# Sheet1.net
KiCad netlist of a schematic drawn in Altium Designer
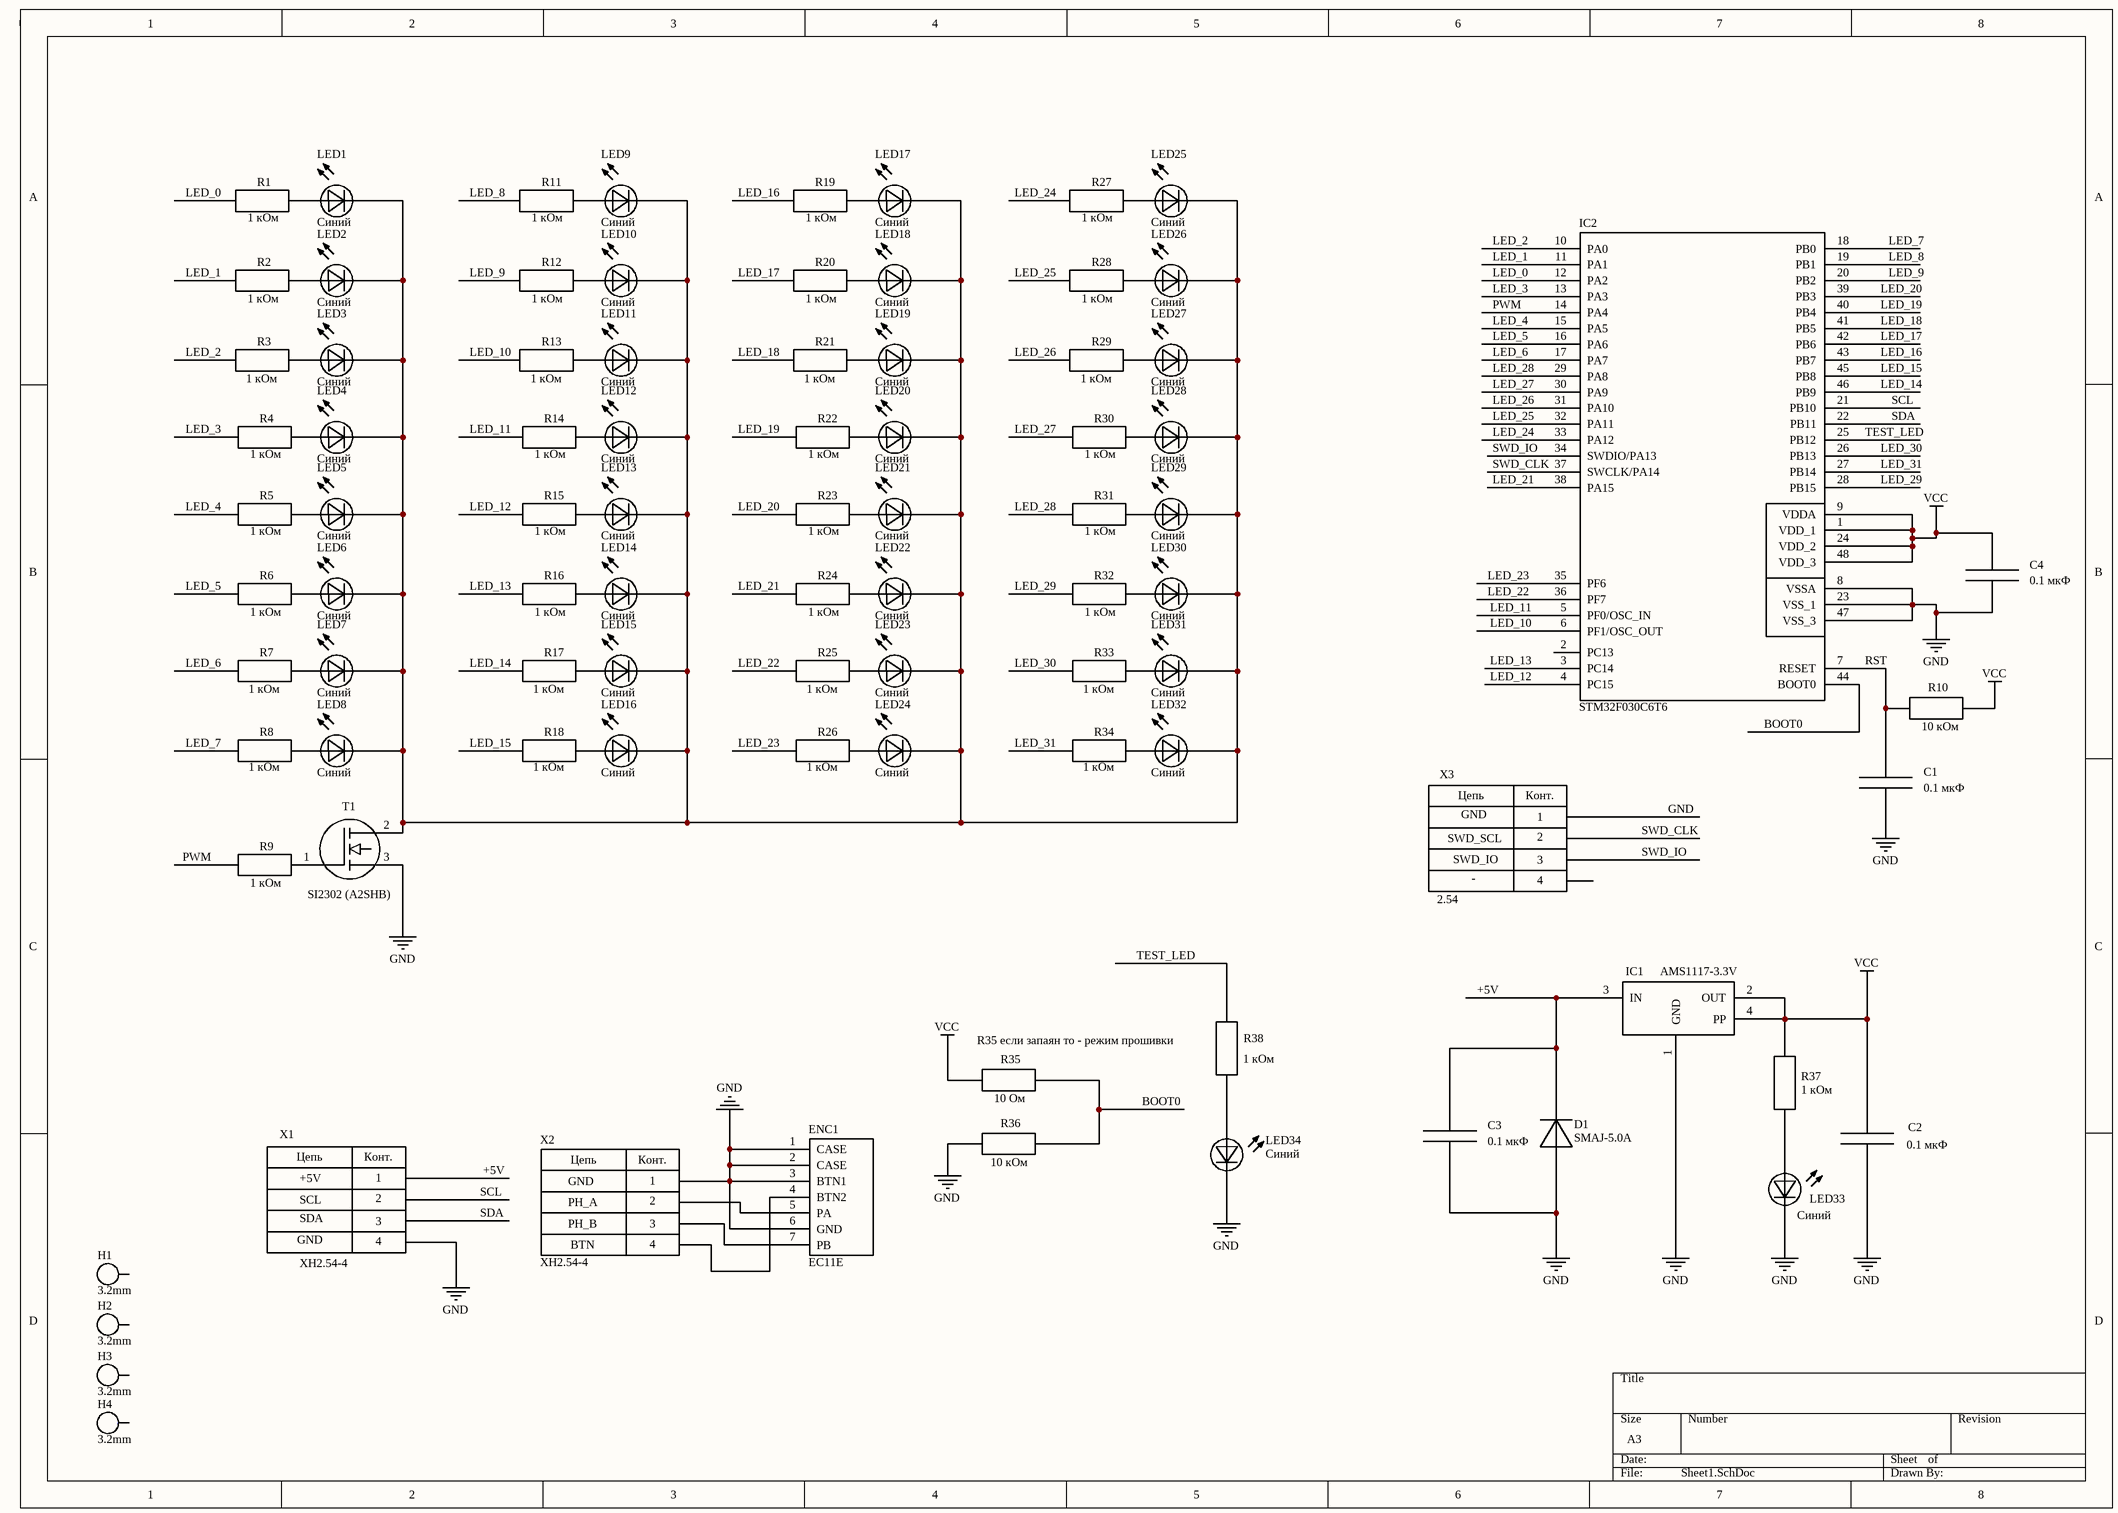
[diagram p0: Sheet1.SchDoc]

(export (version "E")
  (design (tool "Eeschema 10.0.6"))
  (components
    (comp (ref "C1")
      (value "0.1 мкФ")
      (footprint "Конденсатор SMD Case 0805")
      (libsource (lib "S83") (part "Конденсатор"))
    )
    (comp (ref "C2")
      (value "0.1 мкФ")
      (footprint "Конденсатор SMD Case 1206")
      (libsource (lib "S83") (part "Конденсатор"))
    )
    (comp (ref "C3")
      (value "0.1 мкФ")
      (footprint "Конденсатор SMD Case 0805")
      (libsource (lib "S83") (part "Конденсатор"))
    )
    (comp (ref "C4")
      (value "0.1 мкФ")
      (footprint "Конденсатор SMD Case 0805")
      (libsource (lib "S83") (part "Конденсатор"))
    )
    (comp (ref "D1") (value "SMAJ-5.0A") (footprint "Диод SS14") (libsource (lib "S83") (part "Диод")))
    (comp (ref "ENC1") (value "EC11E") (footprint "Encoder") (libsource (lib "S83") (part "Encoder_01")))
    (comp (ref "H1")
      (value "3.2mm")
      (footprint "Отверстие 3,2")
      (libsource (lib "S83") (part "Отверстие монтажное"))
    )
    (comp (ref "H2")
      (value "3.2mm")
      (footprint "Отверстие 3,2")
      (libsource (lib "S83") (part "Отверстие монтажное"))
    )
    (comp (ref "H3")
      (value "3.2mm")
      (footprint "Отверстие 3,2")
      (libsource (lib "S83") (part "Отверстие монтажное"))
    )
    (comp (ref "H4")
      (value "3.2mm")
      (footprint "Отверстие 3,2")
      (libsource (lib "S83") (part "Отверстие монтажное"))
    )
    (comp (ref "IC1")
      (value "AMS1117-3.3V")
      (footprint "SOT-223")
      (libsource (lib "S83_IC") (part "AMS1117"))
    )
    (comp (ref "IC2")
      (value "STM32F030С6T6")
      (footprint "TQFP-48")
      (libsource (lib "S83_IC") (part "STM32F030"))
    )
    (comp (ref "LED1")
      (value "Синий")
      (footprint "Светодиод  3x2 mm")
      (libsource (lib "S83") (part "Светодиод"))
    )
    (comp (ref "LED2")
      (value "Синий")
      (footprint "Светодиод  3x2 mm")
      (libsource (lib "S83") (part "Светодиод"))
    )
    (comp (ref "LED3")
      (value "Синий")
      (footprint "Светодиод  3x2 mm")
      (libsource (lib "S83") (part "Светодиод"))
    )
    (comp (ref "LED4")
      (value "Синий")
      (footprint "Светодиод  3x2 mm")
      (libsource (lib "S83") (part "Светодиод"))
    )
    (comp (ref "LED5")
      (value "Синий")
      (footprint "Светодиод  3x2 mm")
      (libsource (lib "S83") (part "Светодиод"))
    )
    (comp (ref "LED6")
      (value "Синий")
      (footprint "Светодиод  3x2 mm")
      (libsource (lib "S83") (part "Светодиод"))
    )
    (comp (ref "LED7")
      (value "Синий")
      (footprint "Светодиод  3x2 mm")
      (libsource (lib "S83") (part "Светодиод"))
    )
    (comp (ref "LED8")
      (value "Синий")
      (footprint "Светодиод  3x2 mm")
      (libsource (lib "S83") (part "Светодиод"))
    )
    (comp (ref "LED9")
      (value "Синий")
      (footprint "Светодиод  3x2 mm")
      (libsource (lib "S83") (part "Светодиод"))
    )
    (comp (ref "LED10")
      (value "Синий")
      (footprint "Светодиод  3x2 mm")
      (libsource (lib "S83") (part "Светодиод"))
    )
    (comp (ref "LED11")
      (value "Синий")
      (footprint "Светодиод  3x2 mm")
      (libsource (lib "S83") (part "Светодиод"))
    )
    (comp (ref "LED12")
      (value "Синий")
      (footprint "Светодиод  3x2 mm")
      (libsource (lib "S83") (part "Светодиод"))
    )
    (comp (ref "LED13")
      (value "Синий")
      (footprint "Светодиод  3x2 mm")
      (libsource (lib "S83") (part "Светодиод"))
    )
    (comp (ref "LED14")
      (value "Синий")
      (footprint "Светодиод  3x2 mm")
      (libsource (lib "S83") (part "Светодиод"))
    )
    (comp (ref "LED15")
      (value "Синий")
      (footprint "Светодиод  3x2 mm")
      (libsource (lib "S83") (part "Светодиод"))
    )
    (comp (ref "LED16")
      (value "Синий")
      (footprint "Светодиод  3x2 mm")
      (libsource (lib "S83") (part "Светодиод"))
    )
    (comp (ref "LED17")
      (value "Синий")
      (footprint "Светодиод  3x2 mm")
      (libsource (lib "S83") (part "Светодиод"))
    )
    (comp (ref "LED18")
      (value "Синий")
      (footprint "Светодиод  3x2 mm")
      (libsource (lib "S83") (part "Светодиод"))
    )
    (comp (ref "LED19")
      (value "Синий")
      (footprint "Светодиод  3x2 mm")
      (libsource (lib "S83") (part "Светодиод"))
    )
    (comp (ref "LED20")
      (value "Синий")
      (footprint "Светодиод  3x2 mm")
      (libsource (lib "S83") (part "Светодиод"))
    )
    (comp (ref "LED21")
      (value "Синий")
      (footprint "Светодиод  3x2 mm")
      (libsource (lib "S83") (part "Светодиод"))
    )
    (comp (ref "LED22")
      (value "Синий")
      (footprint "Светодиод  3x2 mm")
      (libsource (lib "S83") (part "Светодиод"))
    )
    (comp (ref "LED23")
      (value "Синий")
      (footprint "Светодиод  3x2 mm")
      (libsource (lib "S83") (part "Светодиод"))
    )
    (comp (ref "LED24")
      (value "Синий")
      (footprint "Светодиод  3x2 mm")
      (libsource (lib "S83") (part "Светодиод"))
    )
    (comp (ref "LED25")
      (value "Синий")
      (footprint "Светодиод  3x2 mm")
      (libsource (lib "S83") (part "Светодиод"))
    )
    (comp (ref "LED26")
      (value "Синий")
      (footprint "Светодиод  3x2 mm")
      (libsource (lib "S83") (part "Светодиод"))
    )
    (comp (ref "LED27")
      (value "Синий")
      (footprint "Светодиод  3x2 mm")
      (libsource (lib "S83") (part "Светодиод"))
    )
    (comp (ref "LED28")
      (value "Синий")
      (footprint "Светодиод  3x2 mm")
      (libsource (lib "S83") (part "Светодиод"))
    )
    (comp (ref "LED29")
      (value "Синий")
      (footprint "Светодиод  3x2 mm")
      (libsource (lib "S83") (part "Светодиод"))
    )
    (comp (ref "LED30")
      (value "Синий")
      (footprint "Светодиод  3x2 mm")
      (libsource (lib "S83") (part "Светодиод"))
    )
    (comp (ref "LED31")
      (value "Синий")
      (footprint "Светодиод  3x2 mm")
      (libsource (lib "S83") (part "Светодиод"))
    )
    (comp (ref "LED32")
      (value "Синий")
      (footprint "Светодиод  3x2 mm")
      (libsource (lib "S83") (part "Светодиод"))
    )
    (comp (ref "LED33")
      (value "Синий")
      (footprint "SMD 1206 Светодиод ВАЙТ")
      (libsource (lib "S83") (part "Светодиод"))
    )
    (comp (ref "LED34")
      (value "Синий")
      (footprint "SMD 1206 Светодиод ВАЙТ")
      (libsource (lib "S83") (part "Светодиод"))
    )
    (comp (ref "R1")
      (value "1 кОм")
      (footprint "SMD 0805 Резистор")
      (libsource (lib "S83") (part "Резистор"))
    )
    (comp (ref "R2")
      (value "1 кОм")
      (footprint "SMD 0805 Резистор")
      (libsource (lib "S83") (part "Резистор"))
    )
    (comp (ref "R3")
      (value "1 кОм")
      (footprint "SMD 0805 Резистор")
      (libsource (lib "S83") (part "Резистор"))
    )
    (comp (ref "R4")
      (value "1 кОм")
      (footprint "SMD 0805 Резистор")
      (libsource (lib "S83") (part "Резистор"))
    )
    (comp (ref "R5")
      (value "1 кОм")
      (footprint "SMD 0805 Резистор")
      (libsource (lib "S83") (part "Резистор"))
    )
    (comp (ref "R6")
      (value "1 кОм")
      (footprint "SMD 0805 Резистор")
      (libsource (lib "S83") (part "Резистор"))
    )
    (comp (ref "R7")
      (value "1 кОм")
      (footprint "SMD 0805 Резистор")
      (libsource (lib "S83") (part "Резистор"))
    )
    (comp (ref "R8")
      (value "1 кОм")
      (footprint "SMD 0805 Резистор")
      (libsource (lib "S83") (part "Резистор"))
    )
    (comp (ref "R9")
      (value "1 кОм")
      (footprint "SMD 0805 Резистор")
      (libsource (lib "S83") (part "Резистор"))
    )
    (comp (ref "R10")
      (value "10 кОм")
      (footprint "SMD 0805 Резистор")
      (libsource (lib "S83") (part "Резистор"))
    )
    (comp (ref "R11")
      (value "1 кОм")
      (footprint "SMD 0805 Резистор")
      (libsource (lib "S83") (part "Резистор"))
    )
    (comp (ref "R12")
      (value "1 кОм")
      (footprint "SMD 0805 Резистор")
      (libsource (lib "S83") (part "Резистор"))
    )
    (comp (ref "R13")
      (value "1 кОм")
      (footprint "SMD 0805 Резистор")
      (libsource (lib "S83") (part "Резистор"))
    )
    (comp (ref "R14")
      (value "1 кОм")
      (footprint "SMD 0805 Резистор")
      (libsource (lib "S83") (part "Резистор"))
    )
    (comp (ref "R15")
      (value "1 кОм")
      (footprint "SMD 0805 Резистор")
      (libsource (lib "S83") (part "Резистор"))
    )
    (comp (ref "R16")
      (value "1 кОм")
      (footprint "SMD 0805 Резистор")
      (libsource (lib "S83") (part "Резистор"))
    )
    (comp (ref "R17")
      (value "1 кОм")
      (footprint "SMD 0805 Резистор")
      (libsource (lib "S83") (part "Резистор"))
    )
    (comp (ref "R18")
      (value "1 кОм")
      (footprint "SMD 0805 Резистор")
      (libsource (lib "S83") (part "Резистор"))
    )
    (comp (ref "R19")
      (value "1 кОм")
      (footprint "SMD 0805 Резистор")
      (libsource (lib "S83") (part "Резистор"))
    )
    (comp (ref "R20")
      (value "1 кОм")
      (footprint "SMD 0805 Резистор")
      (libsource (lib "S83") (part "Резистор"))
    )
    (comp (ref "R21")
      (value "1 кОм")
      (footprint "SMD 0805 Резистор")
      (libsource (lib "S83") (part "Резистор"))
    )
    (comp (ref "R22")
      (value "1 кОм")
      (footprint "SMD 0805 Резистор")
      (libsource (lib "S83") (part "Резистор"))
    )
    (comp (ref "R23")
      (value "1 кОм")
      (footprint "SMD 0805 Резистор")
      (libsource (lib "S83") (part "Резистор"))
    )
    (comp (ref "R24")
      (value "1 кОм")
      (footprint "SMD 0805 Резистор")
      (libsource (lib "S83") (part "Резистор"))
    )
    (comp (ref "R25")
      (value "1 кОм")
      (footprint "SMD 0805 Резистор")
      (libsource (lib "S83") (part "Резистор"))
    )
    (comp (ref "R26")
      (value "1 кОм")
      (footprint "SMD 0805 Резистор")
      (libsource (lib "S83") (part "Резистор"))
    )
    (comp (ref "R27")
      (value "1 кОм")
      (footprint "SMD 0805 Резистор")
      (libsource (lib "S83") (part "Резистор"))
    )
    (comp (ref "R28")
      (value "1 кОм")
      (footprint "SMD 0805 Резистор")
      (libsource (lib "S83") (part "Резистор"))
    )
    (comp (ref "R29")
      (value "1 кОм")
      (footprint "SMD 0805 Резистор")
      (libsource (lib "S83") (part "Резистор"))
    )
    (comp (ref "R30")
      (value "1 кОм")
      (footprint "SMD 0805 Резистор")
      (libsource (lib "S83") (part "Резистор"))
    )
    (comp (ref "R31")
      (value "1 кОм")
      (footprint "SMD 0805 Резистор")
      (libsource (lib "S83") (part "Резистор"))
    )
    (comp (ref "R32")
      (value "1 кОм")
      (footprint "SMD 0805 Резистор")
      (libsource (lib "S83") (part "Резистор"))
    )
    (comp (ref "R33")
      (value "1 кОм")
      (footprint "SMD 0805 Резистор")
      (libsource (lib "S83") (part "Резистор"))
    )
    (comp (ref "R34")
      (value "1 кОм")
      (footprint "SMD 0805 Резистор")
      (libsource (lib "S83") (part "Резистор"))
    )
    (comp (ref "R35")
      (value "10 Ом")
      (footprint "SMD 0805 Резистор")
      (libsource (lib "S83") (part "Резистор"))
    )
    (comp (ref "R36")
      (value "10 кОм")
      (footprint "SMD 0805 Резистор")
      (libsource (lib "S83") (part "Резистор"))
    )
    (comp (ref "R37")
      (value "1 кОм")
      (footprint "SMD 0805 Резистор")
      (libsource (lib "S83") (part "Резистор"))
    )
    (comp (ref "R38")
      (value "1 кОм")
      (footprint "SMD 0805 Резистор")
      (libsource (lib "S83") (part "Резистор"))
    )
    (comp (ref "T1")
      (value "SI2302 (A2SHB)")
      (footprint "SMD SOT-23 Транзистор 3 pin")
      (libsource (lib "S83") (part "Транзистор MOSFET N-конал (как n-p-n)"))
    )
    (comp (ref "X1")
      (value "XH2.54-4")
      (footprint "(1x4) PIN XH 2.54 HEADR")
      (libsource (lib "S83_connectors") (part "(1x4) pin XH 2.54 Header"))
    )
    (comp (ref "X2")
      (value "XH2.54-4")
      (footprint "(1x4) PIN XH 2.54 HEADR")
      (libsource (lib "S83_connectors") (part "(1x4) pin XH 2.54 Header"))
    )
    (comp (ref "X3")
      (value "2.54")
      (footprint "(1x4)PIN 2.54 HEADR")
      (libsource (lib "S83_connectors") (part "(1x4) pin XH 2.54 Header"))
    )
  )
  (nets
    (net (code "1") (name "/+5V") (class "Default")
      (node (ref "C3") (pin "1") (pinfunction "+_1") (pintype "passive"))
      (node (ref "D1") (pin "2") (pinfunction "K_2") (pintype "passive"))
      (node (ref "IC1") (pin "3") (pinfunction "IN_3") (pintype "passive"))
      (node (ref "X1") (pin "1") (pinfunction "1_1") (pintype "passive"))
    )
    (net (code "2") (name "/BOOT0") (class "Default")
      (node (ref "IC2") (pin "44") (pinfunction "BOOT0_44") (pintype "passive"))
      (node (ref "R35") (pin "2") (pinfunction "right_2") (pintype "passive"))
      (node (ref "R36") (pin "2") (pinfunction "right_2") (pintype "passive"))
    )
    (net (code "3") (name "/LED_0") (class "Default")
      (node (ref "IC2") (pin "12") (pinfunction "PA2_12") (pintype "passive"))
      (node (ref "R1") (pin "1") (pinfunction "left_1") (pintype "passive"))
    )
    (net (code "4") (name "/LED_1") (class "Default")
      (node (ref "IC2") (pin "11") (pinfunction "PA1_11") (pintype "passive"))
      (node (ref "R2") (pin "1") (pinfunction "left_1") (pintype "passive"))
    )
    (net (code "5") (name "/LED_2") (class "Default")
      (node (ref "IC2") (pin "10") (pinfunction "PA0_10") (pintype "passive"))
      (node (ref "R3") (pin "1") (pinfunction "left_1") (pintype "passive"))
    )
    (net (code "6") (name "/LED_3") (class "Default")
      (node (ref "IC2") (pin "13") (pinfunction "PA3_13") (pintype "passive"))
      (node (ref "R4") (pin "1") (pinfunction "left_1") (pintype "passive"))
    )
    (net (code "7") (name "/LED_4") (class "Default")
      (node (ref "IC2") (pin "15") (pinfunction "PA5_15") (pintype "passive"))
      (node (ref "R5") (pin "1") (pinfunction "left_1") (pintype "passive"))
    )
    (net (code "8") (name "/LED_5") (class "Default")
      (node (ref "IC2") (pin "16") (pinfunction "PA6_16") (pintype "passive"))
      (node (ref "R6") (pin "1") (pinfunction "left_1") (pintype "passive"))
    )
    (net (code "9") (name "/LED_6") (class "Default")
      (node (ref "IC2") (pin "17") (pinfunction "PA7_17") (pintype "passive"))
      (node (ref "R7") (pin "1") (pinfunction "left_1") (pintype "passive"))
    )
    (net (code "10") (name "/LED_7") (class "Default")
      (node (ref "IC2") (pin "18") (pinfunction "PB0_18") (pintype "passive"))
      (node (ref "R8") (pin "1") (pinfunction "left_1") (pintype "passive"))
    )
    (net (code "11") (name "/LED_8") (class "Default")
      (node (ref "IC2") (pin "19") (pinfunction "PB1_19") (pintype "passive"))
      (node (ref "R11") (pin "1") (pinfunction "left_1") (pintype "passive"))
    )
    (net (code "12") (name "/LED_9") (class "Default")
      (node (ref "IC2") (pin "20") (pinfunction "PB2_20") (pintype "passive"))
      (node (ref "R12") (pin "1") (pinfunction "left_1") (pintype "passive"))
    )
    (net (code "13") (name "/LED_10") (class "Default")
      (node (ref "IC2") (pin "6") (pinfunction "PF1/OSC_OUT_6") (pintype "passive"))
      (node (ref "R13") (pin "1") (pinfunction "left_1") (pintype "passive"))
    )
    (net (code "14") (name "/LED_11") (class "Default")
      (node (ref "IC2") (pin "5") (pinfunction "PF0/OSC_IN_5") (pintype "passive"))
      (node (ref "R14") (pin "1") (pinfunction "left_1") (pintype "passive"))
    )
    (net (code "15") (name "/LED_12") (class "Default")
      (node (ref "IC2") (pin "4") (pinfunction "PC15_4") (pintype "passive"))
      (node (ref "R15") (pin "1") (pinfunction "left_1") (pintype "passive"))
    )
    (net (code "16") (name "/LED_13") (class "Default")
      (node (ref "IC2") (pin "3") (pinfunction "PC14_3") (pintype "passive"))
      (node (ref "R16") (pin "1") (pinfunction "left_1") (pintype "passive"))
    )
    (net (code "17") (name "/LED_14") (class "Default")
      (node (ref "IC2") (pin "46") (pinfunction "PB9_46") (pintype "passive"))
      (node (ref "R17") (pin "1") (pinfunction "left_1") (pintype "passive"))
    )
    (net (code "18") (name "/LED_15") (class "Default")
      (node (ref "IC2") (pin "45") (pinfunction "PB8_45") (pintype "passive"))
      (node (ref "R18") (pin "1") (pinfunction "left_1") (pintype "passive"))
    )
    (net (code "19") (name "/LED_16") (class "Default")
      (node (ref "IC2") (pin "43") (pinfunction "PB7_43") (pintype "passive"))
      (node (ref "R19") (pin "1") (pinfunction "left_1") (pintype "passive"))
    )
    (net (code "20") (name "/LED_17") (class "Default")
      (node (ref "IC2") (pin "42") (pinfunction "PB6_42") (pintype "passive"))
      (node (ref "R20") (pin "1") (pinfunction "left_1") (pintype "passive"))
    )
    (net (code "21") (name "/LED_18") (class "Default")
      (node (ref "IC2") (pin "41") (pinfunction "PB5_41") (pintype "passive"))
      (node (ref "R21") (pin "1") (pinfunction "left_1") (pintype "passive"))
    )
    (net (code "22") (name "/LED_19") (class "Default")
      (node (ref "IC2") (pin "40") (pinfunction "PB4_40") (pintype "passive"))
      (node (ref "R22") (pin "1") (pinfunction "left_1") (pintype "passive"))
    )
    (net (code "23") (name "/LED_20") (class "Default")
      (node (ref "IC2") (pin "39") (pinfunction "PB3_39") (pintype "passive"))
      (node (ref "R23") (pin "1") (pinfunction "left_1") (pintype "passive"))
    )
    (net (code "24") (name "/LED_21") (class "Default")
      (node (ref "IC2") (pin "38") (pinfunction "PA15_38") (pintype "passive"))
      (node (ref "R24") (pin "1") (pinfunction "left_1") (pintype "passive"))
    )
    (net (code "25") (name "/LED_22") (class "Default")
      (node (ref "IC2") (pin "36") (pinfunction "PF7_36") (pintype "passive"))
      (node (ref "R25") (pin "1") (pinfunction "left_1") (pintype "passive"))
    )
    (net (code "26") (name "/LED_23") (class "Default")
      (node (ref "IC2") (pin "35") (pinfunction "PF6_35") (pintype "passive"))
      (node (ref "R26") (pin "1") (pinfunction "left_1") (pintype "passive"))
    )
    (net (code "27") (name "/LED_24") (class "Default")
      (node (ref "IC2") (pin "33") (pinfunction "PA12_33") (pintype "passive"))
      (node (ref "R27") (pin "1") (pinfunction "left_1") (pintype "passive"))
    )
    (net (code "28") (name "/LED_25") (class "Default")
      (node (ref "IC2") (pin "32") (pinfunction "PA11_32") (pintype "passive"))
      (node (ref "R28") (pin "1") (pinfunction "left_1") (pintype "passive"))
    )
    (net (code "29") (name "/LED_26") (class "Default")
      (node (ref "IC2") (pin "31") (pinfunction "PA10_31") (pintype "passive"))
      (node (ref "R29") (pin "1") (pinfunction "left_1") (pintype "passive"))
    )
    (net (code "30") (name "/LED_27") (class "Default")
      (node (ref "IC2") (pin "30") (pinfunction "PA9_30") (pintype "passive"))
      (node (ref "R30") (pin "1") (pinfunction "left_1") (pintype "passive"))
    )
    (net (code "31") (name "/LED_28") (class "Default")
      (node (ref "IC2") (pin "29") (pinfunction "PA8_29") (pintype "passive"))
      (node (ref "R31") (pin "1") (pinfunction "left_1") (pintype "passive"))
    )
    (net (code "32") (name "/LED_29") (class "Default")
      (node (ref "IC2") (pin "28") (pinfunction "PB15_28") (pintype "passive"))
      (node (ref "R32") (pin "1") (pinfunction "left_1") (pintype "passive"))
    )
    (net (code "33") (name "/LED_30") (class "Default")
      (node (ref "IC2") (pin "26") (pinfunction "PB13_26") (pintype "passive"))
      (node (ref "R33") (pin "1") (pinfunction "left_1") (pintype "passive"))
    )
    (net (code "34") (name "/LED_31") (class "Default")
      (node (ref "IC2") (pin "27") (pinfunction "PB14_27") (pintype "passive"))
      (node (ref "R34") (pin "1") (pinfunction "left_1") (pintype "passive"))
    )
    (net (code "35") (name "/PWM") (class "Default")
      (node (ref "IC2") (pin "14") (pinfunction "PA4_14") (pintype "passive"))
      (node (ref "R9") (pin "1") (pinfunction "left_1") (pintype "passive"))
    )
    (net (code "36") (name "/RST") (class "Default")
      (node (ref "C1") (pin "1") (pinfunction "+_1") (pintype "passive"))
      (node (ref "IC2") (pin "7") (pinfunction "RESET_7") (pintype "passive"))
      (node (ref "R10") (pin "1") (pinfunction "left_1") (pintype "passive"))
    )
    (net (code "37") (name "/SCL") (class "Default")
      (node (ref "IC2") (pin "21") (pinfunction "PB10_21") (pintype "passive"))
      (node (ref "X1") (pin "2") (pinfunction "2_2") (pintype "passive"))
    )
    (net (code "38") (name "/SDA") (class "Default")
      (node (ref "IC2") (pin "22") (pinfunction "PB11_22") (pintype "passive"))
      (node (ref "X1") (pin "3") (pinfunction "3_3") (pintype "passive"))
    )
    (net (code "39") (name "/SWD_CLK") (class "Default")
      (node (ref "IC2") (pin "37") (pinfunction "SWCLK/PA14_37") (pintype "passive"))
      (node (ref "X3") (pin "2") (pinfunction "2_2") (pintype "passive"))
    )
    (net (code "40") (name "/SWD_IO") (class "Default")
      (node (ref "IC2") (pin "34") (pinfunction "SWDIO/PA13_34") (pintype "passive"))
      (node (ref "X3") (pin "3") (pinfunction "3_3") (pintype "passive"))
    )
    (net (code "41") (name "/TEST_LED") (class "Default")
      (node (ref "IC2") (pin "25") (pinfunction "PB12_25") (pintype "passive"))
      (node (ref "R38") (pin "2") (pinfunction "right_2") (pintype "passive"))
    )
    (net (code "42") (name "GND") (class "Default")
      (node (ref "C1") (pin "2") (pinfunction "-_2") (pintype "passive"))
      (node (ref "C2") (pin "2") (pinfunction "-_2") (pintype "passive"))
      (node (ref "C3") (pin "2") (pinfunction "-_2") (pintype "passive"))
      (node (ref "C4") (pin "2") (pinfunction "-_2") (pintype "passive"))
      (node (ref "D1") (pin "1") (pinfunction "А_1") (pintype "passive"))
      (node (ref "ENC1") (pin "1") (pinfunction "CASE_1") (pintype "passive"))
      (node (ref "ENC1") (pin "2") (pinfunction "CASE_2") (pintype "passive"))
      (node (ref "ENC1") (pin "3") (pinfunction "BTN1_3") (pintype "passive"))
      (node (ref "ENC1") (pin "6") (pinfunction "GND_6") (pintype "passive"))
      (node (ref "IC1") (pin "1") (pinfunction "GND_1") (pintype "passive"))
      (node (ref "IC2") (pin "23") (pinfunction "VSS_1_23") (pintype "passive"))
      (node (ref "IC2") (pin "47") (pinfunction "VSS_3_47") (pintype "passive"))
      (node (ref "IC2") (pin "8") (pinfunction "VSSA_8") (pintype "passive"))
      (node (ref "LED33") (pin "2") (pinfunction "K_2") (pintype "passive"))
      (node (ref "LED34") (pin "2") (pinfunction "K_2") (pintype "passive"))
      (node (ref "R36") (pin "1") (pinfunction "left_1") (pintype "passive"))
      (node (ref "T1") (pin "3") (pinfunction "3_3") (pintype "passive"))
      (node (ref "X1") (pin "4") (pinfunction "4_4") (pintype "passive"))
      (node (ref "X2") (pin "1") (pinfunction "1_1") (pintype "passive"))
      (node (ref "X3") (pin "1") (pinfunction "1_1") (pintype "passive"))
    )
    (net (code "43") (name "Net-(ENC1-BTN2)") (class "Default")
      (node (ref "ENC1") (pin "4") (pinfunction "BTN2_4") (pintype "passive"))
      (node (ref "X2") (pin "4") (pinfunction "4_4") (pintype "passive"))
    )
    (net (code "44") (name "Net-(ENC1-PA)") (class "Default")
      (node (ref "ENC1") (pin "5") (pinfunction "PA_5") (pintype "passive"))
      (node (ref "X2") (pin "2") (pinfunction "2_2") (pintype "passive"))
    )
    (net (code "45") (name "Net-(ENC1-PB)") (class "Default")
      (node (ref "ENC1") (pin "7") (pinfunction "PB_7") (pintype "passive"))
      (node (ref "X2") (pin "3") (pinfunction "3_3") (pintype "passive"))
    )
    (net (code "46") (name "Net-(LED1-K)") (class "Default")
      (node (ref "LED1") (pin "2") (pinfunction "K_2") (pintype "passive"))
      (node (ref "LED10") (pin "2") (pinfunction "K_2") (pintype "passive"))
      (node (ref "LED11") (pin "2") (pinfunction "K_2") (pintype "passive"))
      (node (ref "LED12") (pin "2") (pinfunction "K_2") (pintype "passive"))
      (node (ref "LED13") (pin "2") (pinfunction "K_2") (pintype "passive"))
      (node (ref "LED14") (pin "2") (pinfunction "K_2") (pintype "passive"))
      (node (ref "LED15") (pin "2") (pinfunction "K_2") (pintype "passive"))
      (node (ref "LED16") (pin "2") (pinfunction "K_2") (pintype "passive"))
      (node (ref "LED17") (pin "2") (pinfunction "K_2") (pintype "passive"))
      (node (ref "LED18") (pin "2") (pinfunction "K_2") (pintype "passive"))
      (node (ref "LED19") (pin "2") (pinfunction "K_2") (pintype "passive"))
      (node (ref "LED2") (pin "2") (pinfunction "K_2") (pintype "passive"))
      (node (ref "LED20") (pin "2") (pinfunction "K_2") (pintype "passive"))
      (node (ref "LED21") (pin "2") (pinfunction "K_2") (pintype "passive"))
      (node (ref "LED22") (pin "2") (pinfunction "K_2") (pintype "passive"))
      (node (ref "LED23") (pin "2") (pinfunction "K_2") (pintype "passive"))
      (node (ref "LED24") (pin "2") (pinfunction "K_2") (pintype "passive"))
      (node (ref "LED25") (pin "2") (pinfunction "K_2") (pintype "passive"))
      (node (ref "LED26") (pin "2") (pinfunction "K_2") (pintype "passive"))
      (node (ref "LED27") (pin "2") (pinfunction "K_2") (pintype "passive"))
      (node (ref "LED28") (pin "2") (pinfunction "K_2") (pintype "passive"))
      (node (ref "LED29") (pin "2") (pinfunction "K_2") (pintype "passive"))
      (node (ref "LED3") (pin "2") (pinfunction "K_2") (pintype "passive"))
      (node (ref "LED30") (pin "2") (pinfunction "K_2") (pintype "passive"))
      (node (ref "LED31") (pin "2") (pinfunction "K_2") (pintype "passive"))
      (node (ref "LED32") (pin "2") (pinfunction "K_2") (pintype "passive"))
      (node (ref "LED4") (pin "2") (pinfunction "K_2") (pintype "passive"))
      (node (ref "LED5") (pin "2") (pinfunction "K_2") (pintype "passive"))
      (node (ref "LED6") (pin "2") (pinfunction "K_2") (pintype "passive"))
      (node (ref "LED7") (pin "2") (pinfunction "K_2") (pintype "passive"))
      (node (ref "LED8") (pin "2") (pinfunction "K_2") (pintype "passive"))
      (node (ref "LED9") (pin "2") (pinfunction "K_2") (pintype "passive"))
      (node (ref "T1") (pin "2") (pinfunction "2_2") (pintype "passive"))
    )
    (net (code "47") (name "Net-(LED1-А)") (class "Default")
      (node (ref "LED1") (pin "1") (pinfunction "А_1") (pintype "passive"))
      (node (ref "R1") (pin "2") (pinfunction "right_2") (pintype "passive"))
    )
    (net (code "48") (name "Net-(LED2-А)") (class "Default")
      (node (ref "LED2") (pin "1") (pinfunction "А_1") (pintype "passive"))
      (node (ref "R2") (pin "2") (pinfunction "right_2") (pintype "passive"))
    )
    (net (code "49") (name "Net-(LED3-А)") (class "Default")
      (node (ref "LED3") (pin "1") (pinfunction "А_1") (pintype "passive"))
      (node (ref "R3") (pin "2") (pinfunction "right_2") (pintype "passive"))
    )
    (net (code "50") (name "Net-(LED4-А)") (class "Default")
      (node (ref "LED4") (pin "1") (pinfunction "А_1") (pintype "passive"))
      (node (ref "R4") (pin "2") (pinfunction "right_2") (pintype "passive"))
    )
    (net (code "51") (name "Net-(LED5-А)") (class "Default")
      (node (ref "LED5") (pin "1") (pinfunction "А_1") (pintype "passive"))
      (node (ref "R5") (pin "2") (pinfunction "right_2") (pintype "passive"))
    )
    (net (code "52") (name "Net-(LED6-А)") (class "Default")
      (node (ref "LED6") (pin "1") (pinfunction "А_1") (pintype "passive"))
      (node (ref "R6") (pin "2") (pinfunction "right_2") (pintype "passive"))
    )
    (net (code "53") (name "Net-(LED7-А)") (class "Default")
      (node (ref "LED7") (pin "1") (pinfunction "А_1") (pintype "passive"))
      (node (ref "R7") (pin "2") (pinfunction "right_2") (pintype "passive"))
    )
    (net (code "54") (name "Net-(LED8-А)") (class "Default")
      (node (ref "LED8") (pin "1") (pinfunction "А_1") (pintype "passive"))
      (node (ref "R8") (pin "2") (pinfunction "right_2") (pintype "passive"))
    )
    (net (code "55") (name "Net-(LED9-А)") (class "Default")
      (node (ref "LED9") (pin "1") (pinfunction "А_1") (pintype "passive"))
      (node (ref "R11") (pin "2") (pinfunction "right_2") (pintype "passive"))
    )
    (net (code "56") (name "Net-(LED10-А)") (class "Default")
      (node (ref "LED10") (pin "1") (pinfunction "А_1") (pintype "passive"))
      (node (ref "R12") (pin "2") (pinfunction "right_2") (pintype "passive"))
    )
    (net (code "57") (name "Net-(LED11-А)") (class "Default")
      (node (ref "LED11") (pin "1") (pinfunction "А_1") (pintype "passive"))
      (node (ref "R13") (pin "2") (pinfunction "right_2") (pintype "passive"))
    )
    (net (code "58") (name "Net-(LED12-А)") (class "Default")
      (node (ref "LED12") (pin "1") (pinfunction "А_1") (pintype "passive"))
      (node (ref "R14") (pin "2") (pinfunction "right_2") (pintype "passive"))
    )
    (net (code "59") (name "Net-(LED13-А)") (class "Default")
      (node (ref "LED13") (pin "1") (pinfunction "А_1") (pintype "passive"))
      (node (ref "R15") (pin "2") (pinfunction "right_2") (pintype "passive"))
    )
    (net (code "60") (name "Net-(LED14-А)") (class "Default")
      (node (ref "LED14") (pin "1") (pinfunction "А_1") (pintype "passive"))
      (node (ref "R16") (pin "2") (pinfunction "right_2") (pintype "passive"))
    )
    (net (code "61") (name "Net-(LED15-А)") (class "Default")
      (node (ref "LED15") (pin "1") (pinfunction "А_1") (pintype "passive"))
      (node (ref "R17") (pin "2") (pinfunction "right_2") (pintype "passive"))
    )
    (net (code "62") (name "Net-(LED16-А)") (class "Default")
      (node (ref "LED16") (pin "1") (pinfunction "А_1") (pintype "passive"))
      (node (ref "R18") (pin "2") (pinfunction "right_2") (pintype "passive"))
    )
    (net (code "63") (name "Net-(LED17-А)") (class "Default")
      (node (ref "LED17") (pin "1") (pinfunction "А_1") (pintype "passive"))
      (node (ref "R19") (pin "2") (pinfunction "right_2") (pintype "passive"))
    )
    (net (code "64") (name "Net-(LED18-А)") (class "Default")
      (node (ref "LED18") (pin "1") (pinfunction "А_1") (pintype "passive"))
      (node (ref "R20") (pin "2") (pinfunction "right_2") (pintype "passive"))
    )
    (net (code "65") (name "Net-(LED19-А)") (class "Default")
      (node (ref "LED19") (pin "1") (pinfunction "А_1") (pintype "passive"))
      (node (ref "R21") (pin "2") (pinfunction "right_2") (pintype "passive"))
    )
    (net (code "66") (name "Net-(LED20-А)") (class "Default")
      (node (ref "LED20") (pin "1") (pinfunction "А_1") (pintype "passive"))
      (node (ref "R22") (pin "2") (pinfunction "right_2") (pintype "passive"))
    )
    (net (code "67") (name "Net-(LED21-А)") (class "Default")
      (node (ref "LED21") (pin "1") (pinfunction "А_1") (pintype "passive"))
      (node (ref "R23") (pin "2") (pinfunction "right_2") (pintype "passive"))
    )
    (net (code "68") (name "Net-(LED22-А)") (class "Default")
      (node (ref "LED22") (pin "1") (pinfunction "А_1") (pintype "passive"))
      (node (ref "R24") (pin "2") (pinfunction "right_2") (pintype "passive"))
    )
    (net (code "69") (name "Net-(LED23-А)") (class "Default")
      (node (ref "LED23") (pin "1") (pinfunction "А_1") (pintype "passive"))
      (node (ref "R25") (pin "2") (pinfunction "right_2") (pintype "passive"))
    )
    (net (code "70") (name "Net-(LED24-А)") (class "Default")
      (node (ref "LED24") (pin "1") (pinfunction "А_1") (pintype "passive"))
      (node (ref "R26") (pin "2") (pinfunction "right_2") (pintype "passive"))
    )
    (net (code "71") (name "Net-(LED25-А)") (class "Default")
      (node (ref "LED25") (pin "1") (pinfunction "А_1") (pintype "passive"))
      (node (ref "R27") (pin "2") (pinfunction "right_2") (pintype "passive"))
    )
    (net (code "72") (name "Net-(LED26-А)") (class "Default")
      (node (ref "LED26") (pin "1") (pinfunction "А_1") (pintype "passive"))
      (node (ref "R28") (pin "2") (pinfunction "right_2") (pintype "passive"))
    )
    (net (code "73") (name "Net-(LED27-А)") (class "Default")
      (node (ref "LED27") (pin "1") (pinfunction "А_1") (pintype "passive"))
      (node (ref "R29") (pin "2") (pinfunction "right_2") (pintype "passive"))
    )
    (net (code "74") (name "Net-(LED28-А)") (class "Default")
      (node (ref "LED28") (pin "1") (pinfunction "А_1") (pintype "passive"))
      (node (ref "R30") (pin "2") (pinfunction "right_2") (pintype "passive"))
    )
    (net (code "75") (name "Net-(LED29-А)") (class "Default")
      (node (ref "LED29") (pin "1") (pinfunction "А_1") (pintype "passive"))
      (node (ref "R31") (pin "2") (pinfunction "right_2") (pintype "passive"))
    )
    (net (code "76") (name "Net-(LED30-А)") (class "Default")
      (node (ref "LED30") (pin "1") (pinfunction "А_1") (pintype "passive"))
      (node (ref "R32") (pin "2") (pinfunction "right_2") (pintype "passive"))
    )
    (net (code "77") (name "Net-(LED31-А)") (class "Default")
      (node (ref "LED31") (pin "1") (pinfunction "А_1") (pintype "passive"))
      (node (ref "R33") (pin "2") (pinfunction "right_2") (pintype "passive"))
    )
    (net (code "78") (name "Net-(LED32-А)") (class "Default")
      (node (ref "LED32") (pin "1") (pinfunction "А_1") (pintype "passive"))
      (node (ref "R34") (pin "2") (pinfunction "right_2") (pintype "passive"))
    )
    (net (code "79") (name "Net-(LED33-А)") (class "Default")
      (node (ref "LED33") (pin "1") (pinfunction "А_1") (pintype "passive"))
      (node (ref "R37") (pin "1") (pinfunction "left_1") (pintype "passive"))
    )
    (net (code "80") (name "Net-(LED34-А)") (class "Default")
      (node (ref "LED34") (pin "1") (pinfunction "А_1") (pintype "passive"))
      (node (ref "R38") (pin "1") (pinfunction "left_1") (pintype "passive"))
    )
    (net (code "81") (name "Net-(R9-right)") (class "Default")
      (node (ref "R9") (pin "2") (pinfunction "right_2") (pintype "passive"))
      (node (ref "T1") (pin "1") (pinfunction "1_1") (pintype "passive"))
    )
    (net (code "82") (name "VCC") (class "Default")
      (node (ref "C2") (pin "1") (pinfunction "+_1") (pintype "passive"))
      (node (ref "C4") (pin "1") (pinfunction "+_1") (pintype "passive"))
      (node (ref "IC1") (pin "2") (pinfunction "OUT_2") (pintype "passive"))
      (node (ref "IC1") (pin "4") (pinfunction "PP_4") (pintype "passive"))
      (node (ref "IC2") (pin "1") (pinfunction "VDD_1_1") (pintype "passive"))
      (node (ref "IC2") (pin "24") (pinfunction "VDD_2_24") (pintype "passive"))
      (node (ref "IC2") (pin "48") (pinfunction "VDD_3_48") (pintype "passive"))
      (node (ref "IC2") (pin "9") (pinfunction "VDDA_9") (pintype "passive"))
      (node (ref "R10") (pin "2") (pinfunction "right_2") (pintype "passive"))
      (node (ref "R35") (pin "1") (pinfunction "left_1") (pintype "passive"))
      (node (ref "R37") (pin "2") (pinfunction "right_2") (pintype "passive"))
    )
    (net (code "83") (name "unconnected-(H1-Pad1)") (class "Default")
      (node (ref "H1") (pin "1") (pinfunction "1_1") (pintype "passive"))
    )
    (net (code "84") (name "unconnected-(H2-Pad1)") (class "Default")
      (node (ref "H2") (pin "1") (pinfunction "1_1") (pintype "passive"))
    )
    (net (code "85") (name "unconnected-(H3-Pad1)") (class "Default")
      (node (ref "H3") (pin "1") (pinfunction "1_1") (pintype "passive"))
    )
    (net (code "86") (name "unconnected-(H4-Pad1)") (class "Default")
      (node (ref "H4") (pin "1") (pinfunction "1_1") (pintype "passive"))
    )
    (net (code "87") (name "unconnected-(IC2-PC13-Pad2)") (class "Default")
      (node (ref "IC2") (pin "2") (pinfunction "PC13_2") (pintype "passive"))
    )
    (net (code "88") (name "unconnected-(X3-Pad4)") (class "Default")
      (node (ref "X3") (pin "4") (pinfunction "4_4") (pintype "passive"))
    )
  )
)
